# uno_shield_generic_1.net
KiCad netlist of a schematic drawn in EAGLE
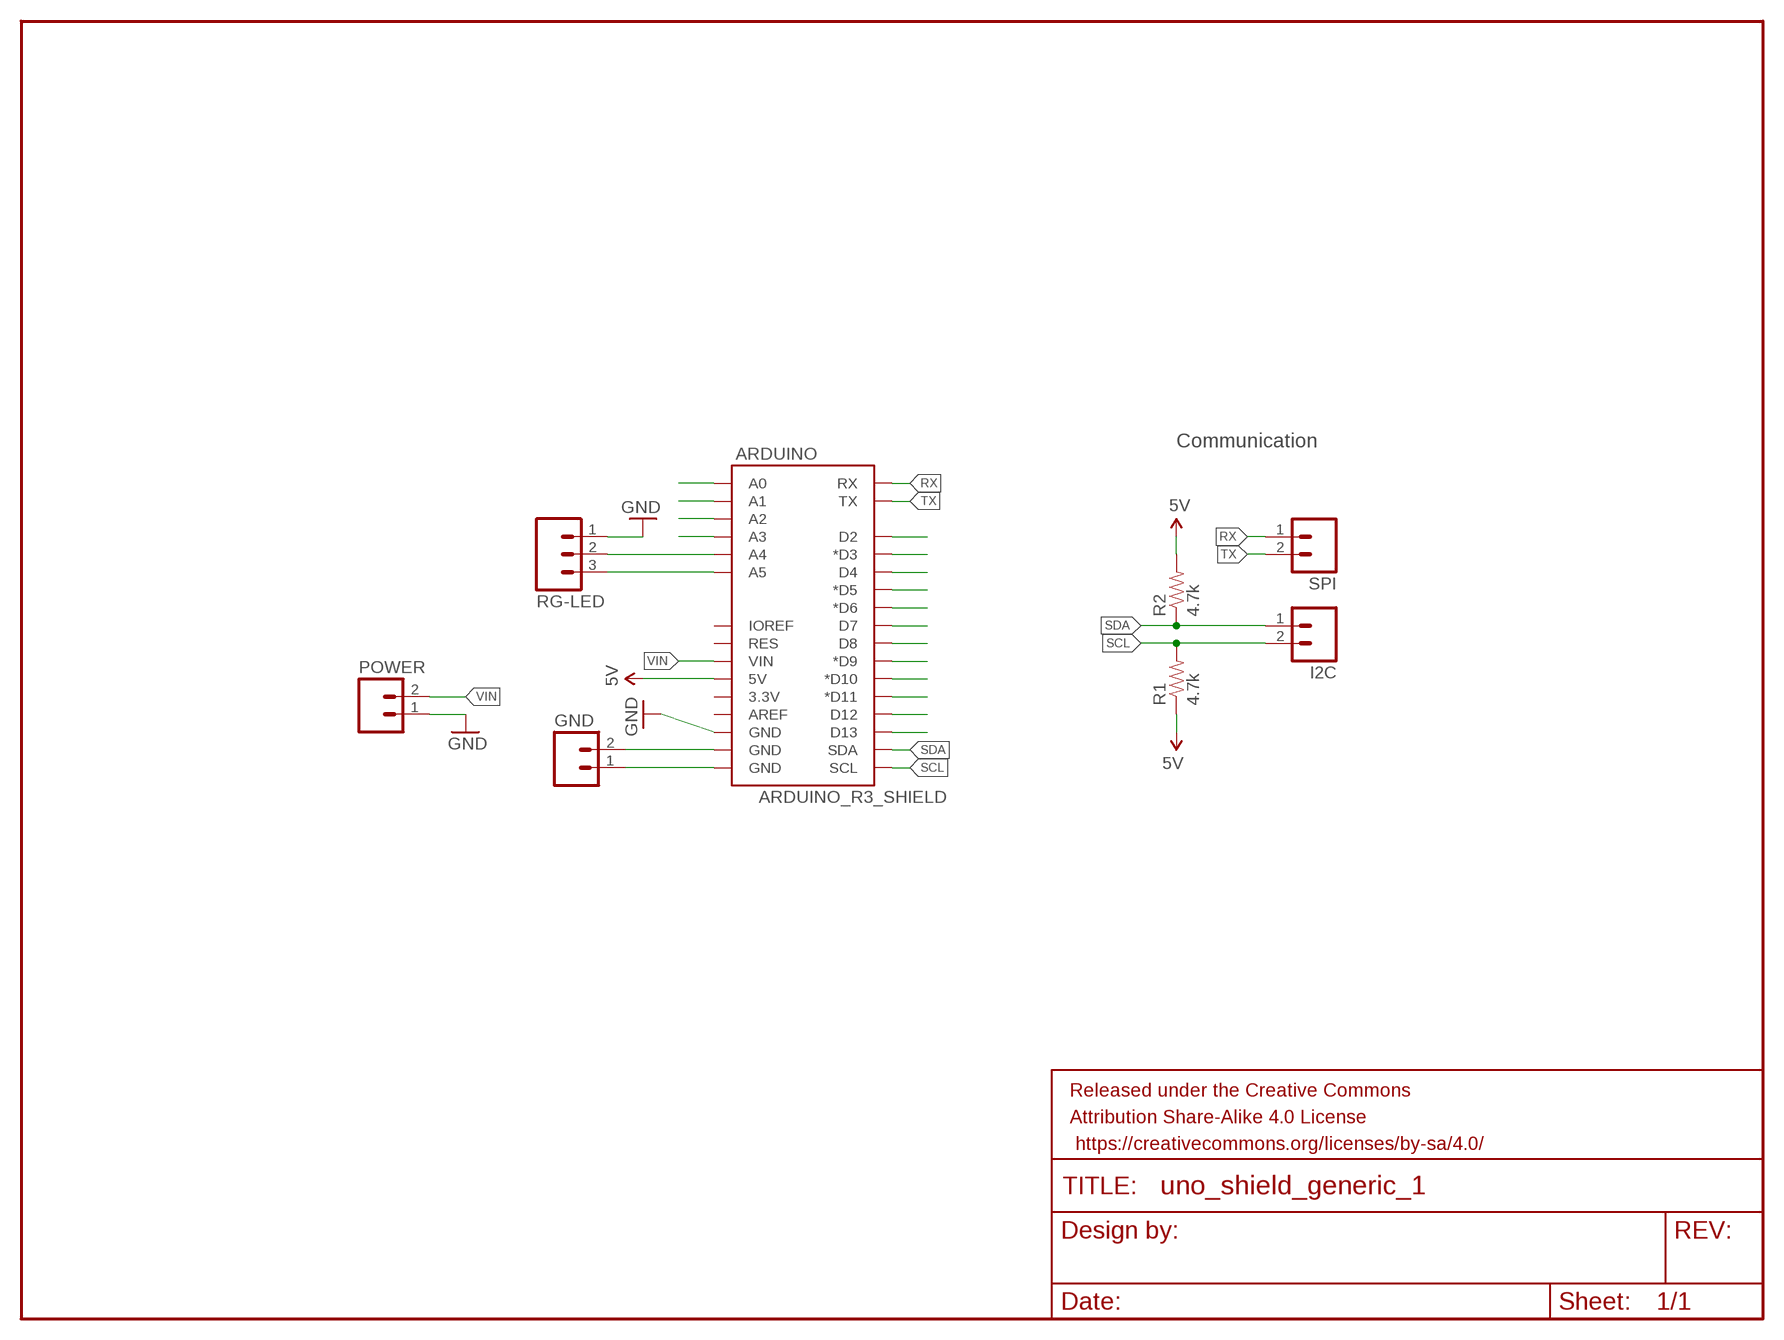
[diagram p0: schematic, sheet 1]

(export (version "E")
  (design (tool "Eeschema 10.0.6"))
  (components
    (comp (ref "ARDUINO")
      (value "ARDUINO_R3_SHIELD")
      (footprint "eagle-import:UNO_R3_SHIELD")
      (libsource (lib "eagle-import") (part "ARDUINO_R3_SHIELD"))
    )
    (comp (ref "FRAME1")
      (value "FRAME-LETTER")
      (footprint "eagle-import:CREATIVE_COMMONS")
      (libsource (lib "eagle-import") (part "FRAME-LETTER"))
    )
    (comp (ref "GND")
      (value "M02LOCK_LONGPADS")
      (footprint "eagle-import:1X02_LOCK_LONGPADS")
      (libsource (lib "eagle-import") (part "M02LOCK_LONGPADS"))
    )
    (comp (ref "I2C")
      (value "M02LOCK_LONGPADS")
      (footprint "eagle-import:1X02_LOCK_LONGPADS")
      (libsource (lib "eagle-import") (part "M02LOCK_LONGPADS"))
    )
    (comp (ref "POWER")
      (value "M02LOCK_LONGPADS")
      (footprint "eagle-import:1X02_LOCK_LONGPADS")
      (libsource (lib "eagle-import") (part "M02LOCK_LONGPADS"))
    )
    (comp (ref "R1")
      (value "4.7k")
      (footprint "eagle-import:AXIAL-0.3-KIT")
      (libsource (lib "eagle-import") (part "RESISTORKIT"))
    )
    (comp (ref "R2")
      (value "4.7k")
      (footprint "eagle-import:AXIAL-0.3-KIT")
      (libsource (lib "eagle-import") (part "RESISTORKIT"))
    )
    (comp (ref "RG-LED")
      (value "M03LONGPADS")
      (footprint "eagle-import:1X03_LONGPADS")
      (libsource (lib "eagle-import") (part "M03LONGPADS"))
    )
    (comp (ref "SPI")
      (value "M02LOCK_LONGPADS")
      (footprint "eagle-import:1X02_LOCK_LONGPADS")
      (libsource (lib "eagle-import") (part "M02LOCK_LONGPADS"))
    )
  )
  (nets
    (net (code "1") (name "5V") (class "Default")
      (node (ref "ARDUINO") (pin "5V") (pinfunction "5V_5V") (pintype "bidirectional"))
      (node (ref "R1") (pin "P$1") (pinfunction "1_P$1") (pintype "passive"))
      (node (ref "R2") (pin "P$2") (pinfunction "2_P$2") (pintype "passive"))
    )
    (net (code "2") (name "GND") (class "Default")
      (node (ref "ARDUINO") (pin "GND@2") (pinfunction "GND_GND@2") (pintype "bidirectional"))
      (node (ref "POWER") (pin "1") (pinfunction "1_1") (pintype "passive"))
      (node (ref "RG-LED") (pin "1") (pinfunction "1_1") (pintype "passive"))
    )
    (net (code "3") (name "Net-(ARDUINO-GND-PadGND@0)") (class "Default")
      (node (ref "ARDUINO") (pin "GND@0") (pinfunction "GND_GND@0") (pintype "bidirectional"))
      (node (ref "GND") (pin "1") (pinfunction "1_1") (pintype "passive"))
    )
    (net (code "4") (name "Net-(ARDUINO-GND-PadGND@1)") (class "Default")
      (node (ref "ARDUINO") (pin "GND@1") (pinfunction "GND_GND@1") (pintype "bidirectional"))
      (node (ref "GND") (pin "2") (pinfunction "2_2") (pintype "passive"))
    )
    (net (code "5") (name "Net-(ARDUINO-PadA4)") (class "Default")
      (node (ref "ARDUINO") (pin "A4") (pinfunction "A4_A4") (pintype "bidirectional"))
      (node (ref "RG-LED") (pin "2") (pinfunction "2_2") (pintype "passive"))
    )
    (net (code "6") (name "Net-(ARDUINO-PadA5)") (class "Default")
      (node (ref "ARDUINO") (pin "A5") (pinfunction "A5_A5") (pintype "bidirectional"))
      (node (ref "RG-LED") (pin "3") (pinfunction "3_3") (pintype "passive"))
    )
    (net (code "7") (name "RX") (class "Default")
      (node (ref "ARDUINO") (pin "RX") (pinfunction "RX_RX") (pintype "bidirectional"))
      (node (ref "SPI") (pin "1") (pinfunction "1_1") (pintype "passive"))
    )
    (net (code "8") (name "SCL") (class "Default")
      (node (ref "ARDUINO") (pin "SCL") (pinfunction "SCL_SCL") (pintype "bidirectional"))
      (node (ref "I2C") (pin "2") (pinfunction "2_2") (pintype "passive"))
      (node (ref "R1") (pin "P$2") (pinfunction "2_P$2") (pintype "passive"))
    )
    (net (code "9") (name "SDA") (class "Default")
      (node (ref "ARDUINO") (pin "SDA") (pinfunction "SDA_SDA") (pintype "bidirectional"))
      (node (ref "I2C") (pin "1") (pinfunction "1_1") (pintype "passive"))
      (node (ref "R2") (pin "P$1") (pinfunction "1_P$1") (pintype "passive"))
    )
    (net (code "10") (name "TX") (class "Default")
      (node (ref "ARDUINO") (pin "TX") (pinfunction "TX_TX") (pintype "bidirectional"))
      (node (ref "SPI") (pin "2") (pinfunction "2_2") (pintype "passive"))
    )
    (net (code "11") (name "VIN") (class "Default")
      (node (ref "ARDUINO") (pin "VIN") (pinfunction "VIN_VIN") (pintype "bidirectional"))
      (node (ref "POWER") (pin "2") (pinfunction "2_2") (pintype "passive"))
    )
    (net (code "12") (name "unconnected-(ARDUINO-*D3-PadD3)") (class "Default")
      (node (ref "ARDUINO") (pin "D3") (pinfunction "*D3_D3") (pintype "bidirectional"))
    )
    (net (code "13") (name "unconnected-(ARDUINO-*D5-PadD5)") (class "Default")
      (node (ref "ARDUINO") (pin "D5") (pinfunction "*D5_D5") (pintype "bidirectional"))
    )
    (net (code "14") (name "unconnected-(ARDUINO-*D6-PadD6)") (class "Default")
      (node (ref "ARDUINO") (pin "D6") (pinfunction "*D6_D6") (pintype "bidirectional"))
    )
    (net (code "15") (name "unconnected-(ARDUINO-*D9-PadD9)") (class "Default")
      (node (ref "ARDUINO") (pin "D9") (pinfunction "*D9_D9") (pintype "bidirectional"))
    )
    (net (code "16") (name "unconnected-(ARDUINO-*D10-PadD10)") (class "Default")
      (node (ref "ARDUINO") (pin "D10") (pinfunction "*D10_D10") (pintype "bidirectional"))
    )
    (net (code "17") (name "unconnected-(ARDUINO-*D11-PadD11)") (class "Default")
      (node (ref "ARDUINO") (pin "D11") (pinfunction "*D11_D11") (pintype "bidirectional"))
    )
    (net (code "18") (name "unconnected-(ARDUINO-Pad3.3V)") (class "Default")
      (node (ref "ARDUINO") (pin "3.3V") (pinfunction "3.3V_3.3V") (pintype "bidirectional"))
    )
    (net (code "19") (name "unconnected-(ARDUINO-PadA0)") (class "Default")
      (node (ref "ARDUINO") (pin "A0") (pinfunction "A0_A0") (pintype "bidirectional"))
    )
    (net (code "20") (name "unconnected-(ARDUINO-PadA1)") (class "Default")
      (node (ref "ARDUINO") (pin "A1") (pinfunction "A1_A1") (pintype "bidirectional"))
    )
    (net (code "21") (name "unconnected-(ARDUINO-PadA2)") (class "Default")
      (node (ref "ARDUINO") (pin "A2") (pinfunction "A2_A2") (pintype "bidirectional"))
    )
    (net (code "22") (name "unconnected-(ARDUINO-PadA3)") (class "Default")
      (node (ref "ARDUINO") (pin "A3") (pinfunction "A3_A3") (pintype "bidirectional"))
    )
    (net (code "23") (name "unconnected-(ARDUINO-PadAREF)") (class "Default")
      (node (ref "ARDUINO") (pin "AREF") (pinfunction "AREF_AREF") (pintype "bidirectional"))
    )
    (net (code "24") (name "unconnected-(ARDUINO-PadD2)") (class "Default")
      (node (ref "ARDUINO") (pin "D2") (pinfunction "D2_D2") (pintype "bidirectional"))
    )
    (net (code "25") (name "unconnected-(ARDUINO-PadD4)") (class "Default")
      (node (ref "ARDUINO") (pin "D4") (pinfunction "D4_D4") (pintype "bidirectional"))
    )
    (net (code "26") (name "unconnected-(ARDUINO-PadD7)") (class "Default")
      (node (ref "ARDUINO") (pin "D7") (pinfunction "D7_D7") (pintype "bidirectional"))
    )
    (net (code "27") (name "unconnected-(ARDUINO-PadD8)") (class "Default")
      (node (ref "ARDUINO") (pin "D8") (pinfunction "D8_D8") (pintype "bidirectional"))
    )
    (net (code "28") (name "unconnected-(ARDUINO-PadD12)") (class "Default")
      (node (ref "ARDUINO") (pin "D12") (pinfunction "D12_D12") (pintype "bidirectional"))
    )
    (net (code "29") (name "unconnected-(ARDUINO-PadD13)") (class "Default")
      (node (ref "ARDUINO") (pin "D13") (pinfunction "D13_D13") (pintype "bidirectional"))
    )
    (net (code "30") (name "unconnected-(ARDUINO-PadIOREF)") (class "Default")
      (node (ref "ARDUINO") (pin "IOREF") (pinfunction "IOREF_IOREF") (pintype "bidirectional"))
    )
    (net (code "31") (name "unconnected-(ARDUINO-PadRES)") (class "Default")
      (node (ref "ARDUINO") (pin "RES") (pinfunction "RES_RES") (pintype "bidirectional"))
    )
  )
)
